# Bee-CC2540.net
KiCad netlist of a schematic drawn in Altium Designer
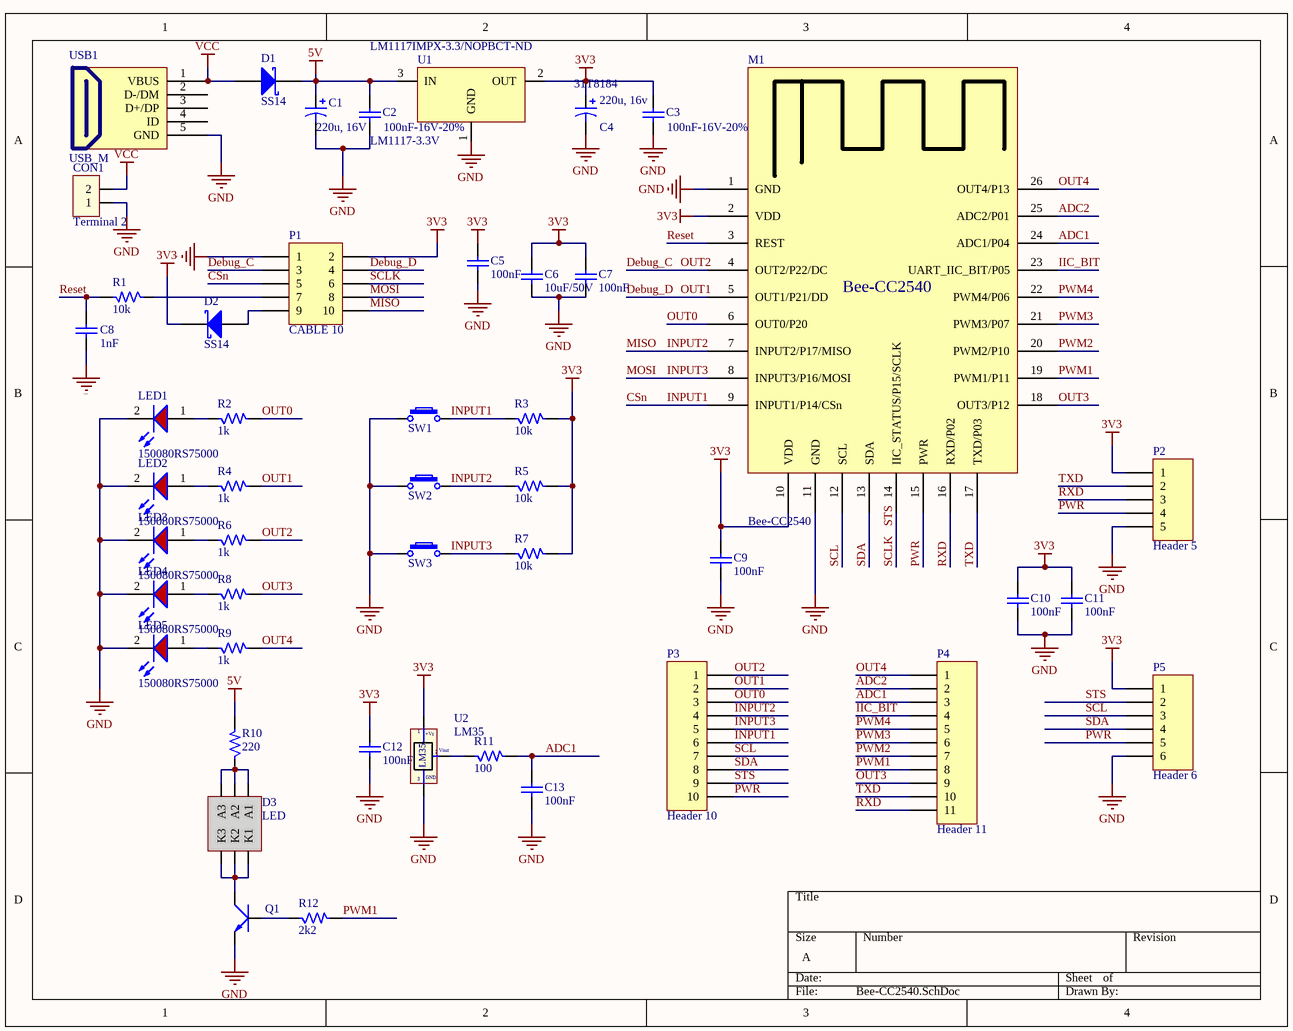
[diagram p0: Bee-CC2540.SchDoc]

(export (version "E")
  (design (tool "Eeschema 10.0.6"))
  (components
    (comp (ref "C1")
      (value "220u, 16V")
      (footprint "ST:CAP TANTALUM 7343")
      (description "Polarized Capacitor (Surface Mount)")
      (fields
        (field (name "MANUFACTURER") "Kemet")
        (field (name "MANUFACTURER PART NUMBER") "C0603C103K5RACTU")
        (field (name "PUBLISHER") "Altium Limited")
      )
      (libsource (lib "Miscellaneous Devices") (part "Cap Pol3"))
    )
    (comp (ref "C2")
      (value "100nF-16V-20%")
      (footprint "C0805")
      (description "CAP CER 0.1UF 16V Y5V 0603")
      (fields
        (field (name "MANUFACTURER") "Yageo")
        (field (name "DIGI-KEY PART NUMBER") "311-1369-1-ND")
        (field (name "PUBLISHER") "Altium Limited")
      )
      (libsource (lib "Miscellaneous Devices") (part "Cap"))
    )
    (comp (ref "C3")
      (value "100nF-16V-20%")
      (footprint "C0805")
      (description "CAP CER 0.1UF 16V Y5V 0603")
      (fields
        (field (name "MANUFACTURER") "Yageo")
        (field (name "DIGI-KEY PART NUMBER") "311-1369-1-ND")
        (field (name "PUBLISHER") "Altium Limited")
      )
      (libsource (lib "Miscellaneous Devices") (part "Cap"))
    )
    (comp (ref "C4")
      (value "220u, 16v")
      (footprint "CAP TANTALUM 7343")
      (description "Polarized Capacitor (Surface Mount)")
      (fields (field (name "SUPPLIER PART NUMBER 1") "31T8184") (field (name "PUBLISHER") "Altium Limited"))
      (libsource (lib "Miscellaneous Devices") (part "Cap Pol3"))
    )
    (comp (ref "C5")
      (value "100nF")
      (footprint "C0805")
      (description "CAP CER 0.1UF 16V Y5V 0603")
      (fields
        (field (name "MANUFACTURER") "Yageo")
        (field (name "DIGI-KEY PART NUMBER") "311-1369-1-ND")
        (field (name "PUBLISHER") "Altium Limited")
      )
      (libsource (lib "Miscellaneous Devices") (part "Cap"))
    )
    (comp (ref "C6")
      (value "10uF/50V")
      (footprint "C1206")
      (description "Capacitor 100n 16V 0603")
      (fields (field (name "PUBLISHER") "Altium Limited"))
      (libsource (lib "Capacitor") (part "Cap Semi"))
    )
    (comp (ref "C7")
      (value "100nF")
      (footprint "C0805")
      (description "CAP CER 0.1UF 16V Y5V 0603")
      (fields
        (field (name "MANUFACTURER") "Yageo")
        (field (name "DIGI-KEY PART NUMBER") "311-1369-1-ND")
        (field (name "PUBLISHER") "Altium Limited")
      )
      (libsource (lib "Miscellaneous Devices") (part "Cap"))
    )
    (comp (ref "C8")
      (value "1nF")
      (footprint "C0805")
      (description "CAP CER 0.1UF 16V Y5V 0603")
      (fields
        (field (name "MANUFACTURER") "Yageo")
        (field (name "DIGI-KEY PART NUMBER") "311-1369-1-ND")
        (field (name "PUBLISHER") "Altium Limited")
      )
      (libsource (lib "Miscellaneous Devices") (part "Cap"))
    )
    (comp (ref "C9")
      (value "100nF")
      (footprint "C0805")
      (description "CAP CER 0.1UF 16V Y5V 0603")
      (fields
        (field (name "MANUFACTURER") "Yageo")
        (field (name "DIGI-KEY PART NUMBER") "311-1369-1-ND")
        (field (name "PUBLISHER") "Altium Limited")
      )
      (libsource (lib "Miscellaneous Devices") (part "Cap"))
    )
    (comp (ref "C10")
      (value "100nF")
      (footprint "C0805")
      (description "CAP CER 0.1UF 16V Y5V 0603")
      (fields
        (field (name "MANUFACTURER") "Yageo")
        (field (name "DIGI-KEY PART NUMBER") "311-1369-1-ND")
        (field (name "PUBLISHER") "Altium Limited")
      )
      (libsource (lib "Miscellaneous Devices") (part "Cap"))
    )
    (comp (ref "C11")
      (value "100nF")
      (footprint "C0805")
      (description "CAP CER 0.1UF 16V Y5V 0603")
      (fields
        (field (name "MANUFACTURER") "Yageo")
        (field (name "DIGI-KEY PART NUMBER") "311-1369-1-ND")
        (field (name "PUBLISHER") "Altium Limited")
      )
      (libsource (lib "Miscellaneous Devices") (part "Cap"))
    )
    (comp (ref "C12")
      (value "100nF")
      (footprint "C0805")
      (description "CAP CER 0.1UF 16V Y5V 0603")
      (fields
        (field (name "MANUFACTURER") "Yageo")
        (field (name "DIGI-KEY PART NUMBER") "311-1369-1-ND")
        (field (name "PUBLISHER") "Altium Limited")
      )
      (libsource (lib "Miscellaneous Devices") (part "Cap"))
    )
    (comp (ref "C13")
      (value "100nF")
      (footprint "C0805")
      (description "CAP CER 0.1UF 16V Y5V 0603")
      (fields
        (field (name "MANUFACTURER") "Yageo")
        (field (name "DIGI-KEY PART NUMBER") "311-1369-1-ND")
        (field (name "PUBLISHER") "Altium Limited")
      )
      (libsource (lib "Miscellaneous Devices") (part "Cap"))
    )
    (comp (ref "CON1")
      (value "Terminal 2")
      (footprint "Terminal 2 5.08")
      (libsource (lib "SS_Con") (part "Terminal 2"))
    )
    (comp (ref "D1")
      (value "SS14")
      (footprint "DO-214AC (SMA)")
      (description "Schottky Diode")
      (fields (field (name "PUBLISHER") "Altium Limited"))
      (libsource (lib "Miscellaneous Devices") (part "D Schottky"))
    )
    (comp (ref "D2")
      (value "SS14")
      (footprint "DO-214AC (SMA)")
      (description "Schottky Diode")
      (fields (field (name "PUBLISHER") "Altium Limited"))
      (libsource (lib "Miscellaneous Devices") (part "D Schottky"))
    )
    (comp (ref "D3") (value "LED") (footprint "LED5050") (libsource (lib "diode") (part "LED5050")))
    (comp (ref "LED1")
      (value "150080RS75000")
      (footprint "LED_0805_Red")
      (description "SMD mono-color Chip LED, WL-SMCW, Red")
      (fields
        (field (name "MANUFACTURER") "W黵th Elektronik eiSos GmbH")
        (field (name "CREATED BY") "Christin Otto")
      )
      (libsource (lib "led-lib") (part "led-0805"))
    )
    (comp (ref "LED2")
      (value "150080RS75000")
      (footprint "LED_0805_Red")
      (description "SMD mono-color Chip LED, WL-SMCW, Red")
      (fields
        (field (name "MANUFACTURER") "W黵th Elektronik eiSos GmbH")
        (field (name "CREATED BY") "Christin Otto")
      )
      (libsource (lib "led-lib") (part "led-0805"))
    )
    (comp (ref "LED3")
      (value "150080RS75000")
      (footprint "LED_0805_Red")
      (description "SMD mono-color Chip LED, WL-SMCW, Red")
      (fields
        (field (name "MANUFACTURER") "W黵th Elektronik eiSos GmbH")
        (field (name "CREATED BY") "Christin Otto")
      )
      (libsource (lib "led-lib") (part "led-0805"))
    )
    (comp (ref "LED4")
      (value "150080RS75000")
      (footprint "LED_0805_Red")
      (description "SMD mono-color Chip LED, WL-SMCW, Red")
      (fields
        (field (name "MANUFACTURER") "W黵th Elektronik eiSos GmbH")
        (field (name "CREATED BY") "Christin Otto")
      )
      (libsource (lib "led-lib") (part "led-0805"))
    )
    (comp (ref "LED5")
      (value "150080RS75000")
      (footprint "LED_0805_Red")
      (description "SMD mono-color Chip LED, WL-SMCW, Red")
      (fields
        (field (name "MANUFACTURER") "W黵th Elektronik eiSos GmbH")
        (field (name "CREATED BY") "Christin Otto")
      )
      (libsource (lib "led-lib") (part "led-0805"))
    )
    (comp (ref "M1")
      (value "Bee-CC2540")
      (footprint "PcbLib1:Bee-CC2540")
      (libsource (lib "Schlib1") (part "Bee-CC2540"))
    )
    (comp (ref "P1")
      (value "CABLE 10")
      (footprint "CABLE 10")
      (description "Header, 5-Pin, Dual row")
      (fields (field (name "PUBLISHER") "Altium Limited"))
      (libsource (lib "mLibrary") (part "CABLE 10"))
    )
    (comp (ref "P2")
      (value "Header 5")
      (footprint "HDR1X5")
      (description "Header, 5-Pin")
      (fields (field (name "PUBLISHER") "Altium Limited"))
      (libsource (lib "SS_Con") (part "Header 5"))
    )
    (comp (ref "P3")
      (value "Header 10")
      (footprint "HDR1X10")
      (description "Header, 10-Pin")
      (fields (field (name "PUBLISHER") "Altium Limited"))
      (libsource (lib "SS_Con") (part "Header 10"))
    )
    (comp (ref "P4")
      (value "Header 11")
      (footprint "SS_Con:HDR1X11")
      (description "Header, 11-Pin")
      (fields (field (name "PUBLISHER") "Altium Limited"))
      (libsource (lib "SS_Con") (part "Header 11"))
    )
    (comp (ref "P5")
      (value "Header 6")
      (footprint "HDR1X6")
      (description "Header, 6-Pin")
      (fields (field (name "PUBLISHER") "Altium Limited"))
      (libsource (lib "SS_Con") (part "Header 6"))
    )
    (comp (ref "Q1")
      (value "C1815")
      (footprint "2SC1815")
      (description "NPN SMD Transistor")
      (fields (field (name "MANUFACTURER") "Toshiba"))
      (libsource (lib "ST") (part "C1815"))
    )
    (comp (ref "R1")
      (value "10k")
      (footprint "R0805")
      (description "Resistor SMD")
      (fields (field (name "MANUFACTURER") "UniOhm"))
      (libsource (lib "Schlib1") (part "RM"))
    )
    (comp (ref "R2")
      (value "1k")
      (footprint "R0805")
      (description "Resistor SMD")
      (fields (field (name "MANUFACTURER") "UniOhm"))
      (libsource (lib "Schlib1") (part "RM"))
    )
    (comp (ref "R3")
      (value "10k")
      (footprint "R0805")
      (description "Resistor SMD")
      (fields (field (name "MANUFACTURER") "UniOhm"))
      (libsource (lib "Schlib1") (part "RM"))
    )
    (comp (ref "R4")
      (value "1k")
      (footprint "R0805")
      (description "Resistor SMD")
      (fields (field (name "MANUFACTURER") "UniOhm"))
      (libsource (lib "Schlib1") (part "RM"))
    )
    (comp (ref "R5")
      (value "10k")
      (footprint "R0805")
      (description "Resistor SMD")
      (fields (field (name "MANUFACTURER") "UniOhm"))
      (libsource (lib "Schlib1") (part "RM"))
    )
    (comp (ref "R6")
      (value "1k")
      (footprint "R0805")
      (description "Resistor SMD")
      (fields (field (name "MANUFACTURER") "UniOhm"))
      (libsource (lib "Schlib1") (part "RM"))
    )
    (comp (ref "R7")
      (value "10k")
      (footprint "R0805")
      (description "Resistor SMD")
      (fields (field (name "MANUFACTURER") "UniOhm"))
      (libsource (lib "Schlib1") (part "RM"))
    )
    (comp (ref "R8")
      (value "1k")
      (footprint "R0805")
      (description "Resistor SMD")
      (fields (field (name "MANUFACTURER") "UniOhm"))
      (libsource (lib "Schlib1") (part "RM"))
    )
    (comp (ref "R9")
      (value "1k")
      (footprint "R0805")
      (description "Resistor SMD")
      (fields (field (name "MANUFACTURER") "UniOhm"))
      (libsource (lib "Schlib1") (part "RM"))
    )
    (comp (ref "R10")
      (value "220")
      (footprint "R1206")
      (description "Resistor SMD")
      (fields (field (name "MANUFACTURER") "UniOhm"))
      (libsource (lib "Schlib1") (part "RM"))
    )
    (comp (ref "R11")
      (value "100")
      (footprint "R0805")
      (description "Resistor SMD")
      (fields (field (name "MANUFACTURER") "UniOhm"))
      (libsource (lib "Schlib1") (part "RM"))
    )
    (comp (ref "R12")
      (value "2k2")
      (footprint "R0805")
      (description "Resistor SMD")
      (fields (field (name "MANUFACTURER") "UniOhm"))
      (libsource (lib "Schlib1") (part "RM"))
    )
    (comp (ref "SW1") (value "SW2") (footprint "SMD(2)") (libsource (lib "SC") (part "SW2")))
    (comp (ref "SW2") (value "SW2") (footprint "SMD(2)") (libsource (lib "SC") (part "SW2")))
    (comp (ref "SW3") (value "SW2") (footprint "SMD(2)") (libsource (lib "SC") (part "SW2")))
    (comp (ref "U1")
      (value "LM1117-3.3V")
      (footprint "LM1117-SOP")
      (description "800mA Low-Dropout Linear Regulator")
      (fields
        (field (name "SUPPLIER PART NUMBER 1") "LM1117IMPX-3.3/NOPBCT-ND")
        (field (name "CREATOR") "Nguyen Ba Bien")
      )
      (libsource (lib "General IC") (part "LM1117"))
    )
    (comp (ref "U2")
      (value "LM35")
      (footprint "QTO-92")
      (description "Teminal")
      (libsource (lib "syhaunguyen") (part "LM35"))
    )
    (comp (ref "USB1") (value "USB_M") (footprint "USB_B_MINI_SMD") (libsource (lib "SS_Con") (part "USB_M")))
  )
  (nets
    (net (code "1") (name "/ADC1") (class "Default")
      (node (ref "C13") (pin "1") (pinfunction "1_1") (pintype "passive"))
      (node (ref "M1") (pin "24") (pinfunction "ADC1/P04_24") (pintype "passive"))
      (node (ref "P4") (pin "3") (pinfunction "3_3") (pintype "passive"))
      (node (ref "R11") (pin "2") (pinfunction "2_2") (pintype "passive"))
    )
    (net (code "2") (name "/ADC2") (class "Default")
      (node (ref "M1") (pin "25") (pinfunction "ADC2/P01_25") (pintype "passive"))
      (node (ref "P4") (pin "2") (pinfunction "2_2") (pintype "passive"))
    )
    (net (code "3") (name "/CSn") (class "Default")
      (node (ref "M1") (pin "9") (pinfunction "INPUT1/P14/CSn_9") (pintype "passive"))
      (node (ref "P1") (pin "5") (pinfunction "5_5") (pintype "passive"))
      (node (ref "P3") (pin "6") (pinfunction "6_6") (pintype "passive"))
      (node (ref "R3") (pin "1") (pinfunction "1_1") (pintype "passive"))
      (node (ref "SW1") (pin "2") (pinfunction "2_2") (pintype "passive"))
    )
    (net (code "4") (name "/Debug_C") (class "Default")
      (node (ref "M1") (pin "4") (pinfunction "OUT2/P22/DC_4") (pintype "passive"))
      (node (ref "P1") (pin "3") (pinfunction "3_3") (pintype "passive"))
      (node (ref "P3") (pin "1") (pinfunction "1_1") (pintype "passive"))
      (node (ref "R6") (pin "2") (pinfunction "2_2") (pintype "passive"))
    )
    (net (code "5") (name "/Debug_D") (class "Default")
      (node (ref "M1") (pin "5") (pinfunction "OUT1/P21/DD_5") (pintype "passive"))
      (node (ref "P1") (pin "4") (pinfunction "4_4") (pintype "passive"))
      (node (ref "P3") (pin "2") (pinfunction "2_2") (pintype "passive"))
      (node (ref "R4") (pin "2") (pinfunction "2_2") (pintype "passive"))
    )
    (net (code "6") (name "/IIC_BIT") (class "Default")
      (node (ref "M1") (pin "23") (pinfunction "UART_IIC_BIT/P05_23") (pintype "passive"))
      (node (ref "P4") (pin "4") (pinfunction "4_4") (pintype "passive"))
    )
    (net (code "7") (name "/INPUT2") (class "Default")
      (node (ref "M1") (pin "7") (pinfunction "INPUT2/P17/MISO_7") (pintype "passive"))
      (node (ref "P1") (pin "10") (pinfunction "10_10") (pintype "passive"))
      (node (ref "P3") (pin "4") (pinfunction "4_4") (pintype "passive"))
      (node (ref "R5") (pin "1") (pinfunction "1_1") (pintype "passive"))
      (node (ref "SW2") (pin "2") (pinfunction "2_2") (pintype "passive"))
    )
    (net (code "8") (name "/INPUT3") (class "Default")
      (node (ref "M1") (pin "8") (pinfunction "INPUT3/P16/MOSI_8") (pintype "passive"))
      (node (ref "P1") (pin "8") (pinfunction "8_8") (pintype "passive"))
      (node (ref "P3") (pin "5") (pinfunction "5_5") (pintype "passive"))
      (node (ref "R7") (pin "1") (pinfunction "1_1") (pintype "passive"))
      (node (ref "SW3") (pin "2") (pinfunction "2_2") (pintype "passive"))
    )
    (net (code "9") (name "/OUT0") (class "Default")
      (node (ref "M1") (pin "6") (pinfunction "OUT0/P20_6") (pintype "passive"))
      (node (ref "P3") (pin "3") (pinfunction "3_3") (pintype "passive"))
      (node (ref "R2") (pin "2") (pinfunction "2_2") (pintype "passive"))
    )
    (net (code "10") (name "/OUT3") (class "Default")
      (node (ref "M1") (pin "18") (pinfunction "OUT3/P12_18") (pintype "passive"))
      (node (ref "P4") (pin "9") (pinfunction "9_9") (pintype "passive"))
      (node (ref "R8") (pin "2") (pinfunction "2_2") (pintype "passive"))
    )
    (net (code "11") (name "/OUT4") (class "Default")
      (node (ref "M1") (pin "26") (pinfunction "OUT4/P13_26") (pintype "passive"))
      (node (ref "P4") (pin "1") (pinfunction "1_1") (pintype "passive"))
      (node (ref "R9") (pin "2") (pinfunction "2_2") (pintype "passive"))
    )
    (net (code "12") (name "/PWM1") (class "Default")
      (node (ref "M1") (pin "19") (pinfunction "PWM1/P11_19") (pintype "passive"))
      (node (ref "P4") (pin "8") (pinfunction "8_8") (pintype "passive"))
      (node (ref "R12") (pin "2") (pinfunction "2_2") (pintype "passive"))
    )
    (net (code "13") (name "/PWM2") (class "Default")
      (node (ref "M1") (pin "20") (pinfunction "PWM2/P10_20") (pintype "passive"))
      (node (ref "P4") (pin "7") (pinfunction "7_7") (pintype "passive"))
    )
    (net (code "14") (name "/PWM3") (class "Default")
      (node (ref "M1") (pin "21") (pinfunction "PWM3/P07_21") (pintype "passive"))
      (node (ref "P4") (pin "6") (pinfunction "6_6") (pintype "passive"))
    )
    (net (code "15") (name "/PWM4") (class "Default")
      (node (ref "M1") (pin "22") (pinfunction "PWM4/P06_22") (pintype "passive"))
      (node (ref "P4") (pin "5") (pinfunction "5_5") (pintype "passive"))
    )
    (net (code "16") (name "/PWR") (class "Default")
      (node (ref "M1") (pin "15") (pinfunction "PWR_15") (pintype "passive"))
      (node (ref "P2") (pin "4") (pinfunction "4_4") (pintype "passive"))
      (node (ref "P3") (pin "10") (pinfunction "10_10") (pintype "passive"))
      (node (ref "P5") (pin "5") (pinfunction "5_5") (pintype "passive"))
    )
    (net (code "17") (name "/RXD") (class "Default")
      (node (ref "M1") (pin "16") (pinfunction "RXD/P02_16") (pintype "passive"))
      (node (ref "P2") (pin "3") (pinfunction "3_3") (pintype "passive"))
      (node (ref "P4") (pin "11") (pinfunction "11_11") (pintype "passive"))
    )
    (net (code "18") (name "/Reset") (class "Default")
      (node (ref "C8") (pin "1") (pinfunction "1_1") (pintype "passive"))
      (node (ref "M1") (pin "3") (pinfunction "REST_3") (pintype "passive"))
      (node (ref "R1") (pin "2") (pinfunction "2_2") (pintype "passive"))
    )
    (net (code "19") (name "/SCL") (class "Default")
      (node (ref "M1") (pin "12") (pinfunction "SCL_12") (pintype "passive"))
      (node (ref "P3") (pin "7") (pinfunction "7_7") (pintype "passive"))
      (node (ref "P5") (pin "3") (pinfunction "3_3") (pintype "passive"))
    )
    (net (code "20") (name "/SCLK") (class "Default")
      (node (ref "M1") (pin "14") (pinfunction "IIC_STATUS/P15/SCLK_14") (pintype "passive"))
      (node (ref "P1") (pin "6") (pinfunction "6_6") (pintype "passive"))
      (node (ref "P3") (pin "9") (pinfunction "9_9") (pintype "passive"))
      (node (ref "P5") (pin "2") (pinfunction "2_2") (pintype "passive"))
    )
    (net (code "21") (name "/SDA") (class "Default")
      (node (ref "M1") (pin "13") (pinfunction "SDA_13") (pintype "passive"))
      (node (ref "P3") (pin "8") (pinfunction "8_8") (pintype "passive"))
      (node (ref "P5") (pin "4") (pinfunction "4_4") (pintype "passive"))
    )
    (net (code "22") (name "/TXD") (class "Default")
      (node (ref "M1") (pin "17") (pinfunction "TXD/P03_17") (pintype "passive"))
      (node (ref "P2") (pin "2") (pinfunction "2_2") (pintype "passive"))
      (node (ref "P4") (pin "10") (pinfunction "10_10") (pintype "passive"))
    )
    (net (code "23") (name "3V3") (class "Default")
      (node (ref "C10") (pin "1") (pinfunction "1_1") (pintype "passive"))
      (node (ref "C11") (pin "1") (pinfunction "1_1") (pintype "passive"))
      (node (ref "C12") (pin "1") (pinfunction "1_1") (pintype "passive"))
      (node (ref "C3") (pin "1") (pinfunction "1_1") (pintype "passive"))
      (node (ref "C4") (pin "1") (pinfunction "1_1") (pintype "passive"))
      (node (ref "C5") (pin "1") (pinfunction "1_1") (pintype "passive"))
      (node (ref "C6") (pin "1") (pinfunction "1_1") (pintype "passive"))
      (node (ref "C7") (pin "1") (pinfunction "1_1") (pintype "passive"))
      (node (ref "C9") (pin "1") (pinfunction "1_1") (pintype "passive"))
      (node (ref "D2") (pin "2") (pinfunction "K_2") (pintype "passive"))
      (node (ref "M1") (pin "10") (pinfunction "VDD_10") (pintype "passive"))
      (node (ref "M1") (pin "2") (pinfunction "VDD_2") (pintype "passive"))
      (node (ref "P1") (pin "2") (pinfunction "2_2") (pintype "passive"))
      (node (ref "P2") (pin "1") (pinfunction "1_1") (pintype "passive"))
      (node (ref "P5") (pin "1") (pinfunction "1_1") (pintype "passive"))
      (node (ref "R3") (pin "2") (pinfunction "2_2") (pintype "passive"))
      (node (ref "R5") (pin "2") (pinfunction "2_2") (pintype "passive"))
      (node (ref "R7") (pin "2") (pinfunction "2_2") (pintype "passive"))
      (node (ref "U1") (pin "2") (pinfunction "OUT_2") (pintype "passive"))
      (node (ref "U2") (pin "1") (pinfunction "+Vs_1") (pintype "passive"))
    )
    (net (code "24") (name "5V") (class "Default")
      (node (ref "C1") (pin "1") (pinfunction "1_1") (pintype "passive"))
      (node (ref "C2") (pin "1") (pinfunction "1_1") (pintype "passive"))
      (node (ref "D1") (pin "2") (pinfunction "K_2") (pintype "passive"))
      (node (ref "R10") (pin "2") (pinfunction "2_2") (pintype "passive"))
      (node (ref "U1") (pin "3") (pinfunction "IN_3") (pintype "passive"))
    )
    (net (code "25") (name "GND") (class "Default")
      (node (ref "C1") (pin "2") (pinfunction "2_2") (pintype "passive"))
      (node (ref "C10") (pin "2") (pinfunction "2_2") (pintype "passive"))
      (node (ref "C11") (pin "2") (pinfunction "2_2") (pintype "passive"))
      (node (ref "C12") (pin "2") (pinfunction "2_2") (pintype "passive"))
      (node (ref "C13") (pin "2") (pinfunction "2_2") (pintype "passive"))
      (node (ref "C2") (pin "2") (pinfunction "2_2") (pintype "passive"))
      (node (ref "C3") (pin "2") (pinfunction "2_2") (pintype "passive"))
      (node (ref "C4") (pin "2") (pinfunction "2_2") (pintype "passive"))
      (node (ref "C5") (pin "2") (pinfunction "2_2") (pintype "passive"))
      (node (ref "C6") (pin "2") (pinfunction "2_2") (pintype "passive"))
      (node (ref "C7") (pin "2") (pinfunction "2_2") (pintype "passive"))
      (node (ref "C8") (pin "2") (pinfunction "2_2") (pintype "passive"))
      (node (ref "C9") (pin "2") (pinfunction "2_2") (pintype "passive"))
      (node (ref "CON1") (pin "1") (pinfunction "1_1") (pintype "passive"))
      (node (ref "LED1") (pin "2") (pinfunction "C_2") (pintype "passive"))
      (node (ref "LED2") (pin "2") (pinfunction "C_2") (pintype "passive"))
      (node (ref "LED3") (pin "2") (pinfunction "C_2") (pintype "passive"))
      (node (ref "LED4") (pin "2") (pinfunction "C_2") (pintype "passive"))
      (node (ref "LED5") (pin "2") (pinfunction "C_2") (pintype "passive"))
      (node (ref "M1") (pin "1") (pinfunction "GND_1") (pintype "passive"))
      (node (ref "M1") (pin "11") (pinfunction "GND_11") (pintype "passive"))
      (node (ref "P1") (pin "1") (pinfunction "1_1") (pintype "passive"))
      (node (ref "P2") (pin "5") (pinfunction "5_5") (pintype "passive"))
      (node (ref "P5") (pin "6") (pinfunction "6_6") (pintype "passive"))
      (node (ref "Q1") (pin "2") (pinfunction "E_2") (pintype "passive"))
      (node (ref "SW1") (pin "1") (pinfunction "1_1") (pintype "passive"))
      (node (ref "SW2") (pin "1") (pinfunction "1_1") (pintype "passive"))
      (node (ref "SW3") (pin "1") (pinfunction "1_1") (pintype "passive"))
      (node (ref "U1") (pin "1") (pinfunction "GND_1") (pintype "passive"))
      (node (ref "U2") (pin "3") (pinfunction "-_3") (pintype "passive"))
      (node (ref "USB1") (pin "5") (pinfunction "GND_5") (pintype "passive"))
    )
    (net (code "26") (name "Net-(D2-A)") (class "Default")
      (node (ref "D2") (pin "1") (pinfunction "A_1") (pintype "passive"))
      (node (ref "P1") (pin "9") (pinfunction "9_9") (pintype "passive"))
    )
    (net (code "27") (name "Net-(D3-A1)") (class "Default")
      (node (ref "D3") (pin "1") (pinfunction "A1_1") (pintype "passive"))
      (node (ref "D3") (pin "3") (pinfunction "A2_3") (pintype "passive"))
      (node (ref "D3") (pin "5") (pinfunction "A3_5") (pintype "passive"))
      (node (ref "R10") (pin "1") (pinfunction "1_1") (pintype "passive"))
    )
    (net (code "28") (name "Net-(D3-K1)") (class "Default")
      (node (ref "D3") (pin "2") (pinfunction "K1_2") (pintype "passive"))
      (node (ref "D3") (pin "4") (pinfunction "K2_4") (pintype "passive"))
      (node (ref "D3") (pin "6") (pinfunction "K3_6") (pintype "passive"))
      (node (ref "Q1") (pin "3") (pinfunction "C_3") (pintype "passive"))
    )
    (net (code "29") (name "Net-(LED1-A)") (class "Default")
      (node (ref "LED1") (pin "1") (pinfunction "A_1") (pintype "passive"))
      (node (ref "R2") (pin "1") (pinfunction "1_1") (pintype "passive"))
    )
    (net (code "30") (name "Net-(LED2-A)") (class "Default")
      (node (ref "LED2") (pin "1") (pinfunction "A_1") (pintype "passive"))
      (node (ref "R4") (pin "1") (pinfunction "1_1") (pintype "passive"))
    )
    (net (code "31") (name "Net-(LED3-A)") (class "Default")
      (node (ref "LED3") (pin "1") (pinfunction "A_1") (pintype "passive"))
      (node (ref "R6") (pin "1") (pinfunction "1_1") (pintype "passive"))
    )
    (net (code "32") (name "Net-(LED4-A)") (class "Default")
      (node (ref "LED4") (pin "1") (pinfunction "A_1") (pintype "passive"))
      (node (ref "R8") (pin "1") (pinfunction "1_1") (pintype "passive"))
    )
    (net (code "33") (name "Net-(LED5-A)") (class "Default")
      (node (ref "LED5") (pin "1") (pinfunction "A_1") (pintype "passive"))
      (node (ref "R9") (pin "1") (pinfunction "1_1") (pintype "passive"))
    )
    (net (code "34") (name "Net-(P1-Pad7)") (class "Default")
      (node (ref "P1") (pin "7") (pinfunction "7_7") (pintype "passive"))
      (node (ref "R1") (pin "1") (pinfunction "1_1") (pintype "passive"))
    )
    (net (code "35") (name "Net-(Q1-B)") (class "Default")
      (node (ref "Q1") (pin "1") (pinfunction "B_1") (pintype "passive"))
      (node (ref "R12") (pin "1") (pinfunction "1_1") (pintype "passive"))
    )
    (net (code "36") (name "Net-(U2-Vout)") (class "Default")
      (node (ref "R11") (pin "1") (pinfunction "1_1") (pintype "passive"))
      (node (ref "U2") (pin "2") (pinfunction "Vout_2") (pintype "passive"))
    )
    (net (code "37") (name "VCC") (class "Default")
      (node (ref "CON1") (pin "2") (pinfunction "2_2") (pintype "passive"))
      (node (ref "D1") (pin "1") (pinfunction "A_1") (pintype "passive"))
      (node (ref "USB1") (pin "1") (pinfunction "VBUS_1") (pintype "passive"))
    )
    (net (code "38") (name "unconnected-(USB1-D+{slash}DP-Pad3)") (class "Default")
      (node (ref "USB1") (pin "3") (pinfunction "D+/DP_3") (pintype "passive"))
    )
    (net (code "39") (name "unconnected-(USB1-D-{slash}DM-Pad2)") (class "Default")
      (node (ref "USB1") (pin "2") (pinfunction "D-/DM_2") (pintype "passive"))
    )
    (net (code "40") (name "unconnected-(USB1-ID-Pad4)") (class "Default")
      (node (ref "USB1") (pin "4") (pinfunction "ID_4") (pintype "passive"))
    )
  )
)
